# PSU_MAX1556_DC-DC.net
KiCad netlist of a schematic drawn in Altium Designer
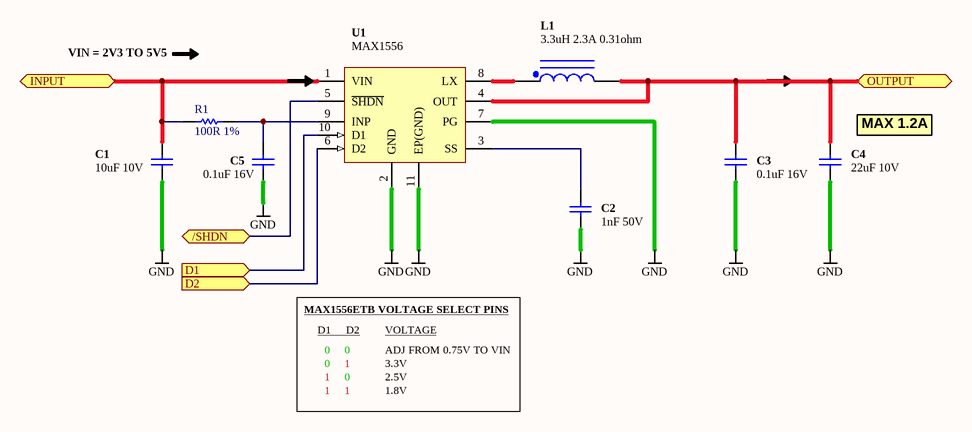
[diagram p0: PSU_MAX1556_DC-DC.SchDoc]

(export (version "E")
  (design (tool "Eeschema 10.0.6"))
  (components
    (comp (ref "C1")
      (value "10uF 10V")
      (footprint "CAPC2012-STAR")
      (description "Capacitor, Ceramic, 10uF 10% 10V 0805 (2012) X5R")
      (fields (field (name "TOLERANCE") "10 %"))
      (libsource (lib "AltiumDesignLibrary") (part "CAP-NP"))
    )
    (comp (ref "C2")
      (value "1nF 50V")
      (footprint "CAPC1005-STAR")
      (description "Capacitor, Ceramic, 1nF 10% 50V 0402 (1005) X7R")
      (fields (field (name "TOLERANCE") "10 %"))
      (libsource (lib "AltiumDesignLibrary") (part "CAP-NP"))
    )
    (comp (ref "C3")
      (value "0.1uF 16V")
      (footprint "CAPC1005-STAR")
      (description "Capacitor, Ceramic, 0.1uF 10% 16V 0402 (1005) X7R")
      (fields (field (name "TOLERANCE") "10 %"))
      (libsource (lib "AltiumDesignLibrary") (part "D-101-0080"))
    )
    (comp (ref "C4")
      (value "22uF 10V")
      (footprint "CAPC3225-STAR")
      (description "Capacitor, Ceramic, 22uF -20%/+80% 10V 1210 (3225) Y5V")
      (fields (field (name "TOLERANCE") "-20 / +80 %"))
      (libsource (lib "AltiumDesignLibrary") (part "CAP-NP"))
    )
    (comp (ref "C5")
      (value "0.1uF 16V")
      (footprint "CAPC1005-STAR")
      (description "Capacitor, Ceramic, 0.1uF 10% 16V 0402 (1005) X7R")
      (fields (field (name "TOLERANCE") "10 %"))
      (libsource (lib "AltiumDesignLibrary") (part "D-101-0080"))
    )
    (comp (ref "L1")
      (value "3.3uH 2.3A 0.31ohm")
      (footprint "B82462G4xxxM")
      (description "Inductor, Chip 3.3uH, 2.3A, 0.31ohm")
      (libsource (lib "AltiumDesignLibrary") (part "IND-IRON-DOT"))
    )
    (comp (ref "R1")
      (value "100R 1%")
      (footprint "RESC1005-STAR")
      (description "Resistor, 100R 1% 0402 (1005)")
      (fields (field (name "TOLERANCE") "1 %"))
      (libsource (lib "AltiumDesignLibrary") (part "RES"))
    )
    (comp (ref "U1")
      (value "MAX1556")
      (footprint "QFN50P300X300X80-10L")
      (description "16uA IQ, 1.2A PWM  Step-Down DC-DC Converters")
      (libsource (lib "AltiumDesignLibrary") (part "MAX1556"))
    )
  )
  (nets
    (net (code "1") (name "/D1") (class "Default")
      (node (ref "U1") (pin "10") (pinfunction "D1_10") (pintype "input"))
    )
    (net (code "2") (name "/D2") (class "Default")
      (node (ref "U1") (pin "6") (pinfunction "D2_6") (pintype "input"))
    )
    (net (code "3") (name "/INPUT") (class "Default")
      (node (ref "C1") (pin "1") (pinfunction "1_1") (pintype "passive"))
      (node (ref "R1") (pin "1") (pinfunction "1_1") (pintype "passive"))
      (node (ref "U1") (pin "1") (pinfunction "VIN_1") (pintype "power_in"))
    )
    (net (code "4") (name "/OUTPUT") (class "Default")
      (node (ref "C3") (pin "2") (pinfunction "2_2") (pintype "passive"))
      (node (ref "C4") (pin "1") (pinfunction "1_1") (pintype "passive"))
      (node (ref "L1") (pin "2") (pinfunction "2_2") (pintype "passive"))
      (node (ref "U1") (pin "4") (pinfunction "OUT_4") (pintype "passive"))
    )
    (net (code "5") (name "/{slash}SHDN") (class "Default")
      (node (ref "U1") (pin "5") (pinfunction "~{SHDN}_5") (pintype "power_in"))
    )
    (net (code "6") (name "GND") (class "Default")
      (node (ref "C1") (pin "2") (pinfunction "2_2") (pintype "passive"))
      (node (ref "C2") (pin "1") (pinfunction "1_1") (pintype "passive"))
      (node (ref "C3") (pin "1") (pinfunction "1_1") (pintype "passive"))
      (node (ref "C4") (pin "2") (pinfunction "2_2") (pintype "passive"))
      (node (ref "C5") (pin "1") (pinfunction "1_1") (pintype "passive"))
      (node (ref "U1") (pin "11") (pinfunction "EP(GND)_11") (pintype "power_in"))
      (node (ref "U1") (pin "2") (pinfunction "GND_2") (pintype "power_in"))
      (node (ref "U1") (pin "7") (pinfunction "PG_7") (pintype "power_in"))
    )
    (net (code "7") (name "Net-(U1-INP)") (class "Default")
      (node (ref "C5") (pin "2") (pinfunction "2_2") (pintype "passive"))
      (node (ref "R1") (pin "2") (pinfunction "2_2") (pintype "passive"))
      (node (ref "U1") (pin "9") (pinfunction "INP_9") (pintype "power_in"))
    )
    (net (code "8") (name "Net-(U1-LX)") (class "Default")
      (node (ref "L1") (pin "1") (pinfunction "1_1") (pintype "passive"))
      (node (ref "U1") (pin "8") (pinfunction "LX_8") (pintype "passive"))
    )
    (net (code "9") (name "Net-(U1-SS)") (class "Default")
      (node (ref "C2") (pin "2") (pinfunction "2_2") (pintype "passive"))
      (node (ref "U1") (pin "3") (pinfunction "SS_3") (pintype "passive"))
    )
  )
)
